# HighSideDriver.net
KiCad netlist of a schematic drawn in Altium Designer
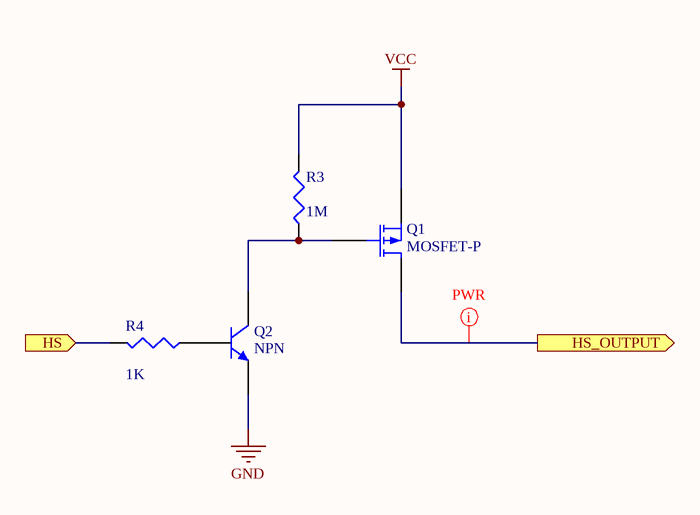
[diagram p0: HighSideDriver.SchDoc]

(export (version "E")
  (design (tool "Eeschema 10.0.6"))
  (components
    (comp (ref "Q1")
      (value "MOSFET-P")
      (footprint "SOT23_M")
      (description "P-Channel MOSFET")
      (fields (field (name "PUBLISHER") "Altium Limited"))
      (libsource (lib "Miscellaneous Devices") (part "MOSFET-P"))
    )
    (comp (ref "Q2")
      (value "NPN")
      (footprint "SOT-23B_M")
      (description "NPN Bipolar Transistor")
      (fields (field (name "PUBLISHER") "Altium Limited"))
      (libsource (lib "Miscellaneous Devices") (part "NPN"))
    )
    (comp (ref "R3")
      (value "1M")
      (footprint "1608[0603]")
      (description "Resistor")
      (fields (field (name "Comment") "Res3") (field (name "PUBLISHER") "Altium Limited"))
      (libsource (lib "Miscellaneous Devices") (part "Res3"))
    )
    (comp (ref "R4")
      (value "1K")
      (footprint "1608[0603]")
      (description "Resistor")
      (fields (field (name "Comment") "Res3") (field (name "PUBLISHER") "Altium Limited"))
      (libsource (lib "Miscellaneous Devices") (part "Res3"))
    )
  )
  (nets
    (net (code "1") (name "/HS") (class "Default")
      (node (ref "R4") (pin "2") (pinfunction "2_2") (pintype "passive"))
    )
    (net (code "2") (name "/HS_OUTPUT") (class "Default")
      (node (ref "Q1") (pin "1") (pinfunction "D_1") (pintype "passive"))
    )
    (net (code "3") (name "GND") (class "Default")
      (node (ref "Q2") (pin "3") (pinfunction "E_3") (pintype "passive"))
    )
    (net (code "4") (name "Net-(Q1-G)") (class "Default")
      (node (ref "Q1") (pin "2") (pinfunction "G_2") (pintype "passive"))
      (node (ref "Q2") (pin "1") (pinfunction "C_1") (pintype "passive"))
      (node (ref "R3") (pin "1") (pinfunction "1_1") (pintype "passive"))
    )
    (net (code "5") (name "Net-(Q2-B)") (class "Default")
      (node (ref "Q2") (pin "2") (pinfunction "B_2") (pintype "passive"))
      (node (ref "R4") (pin "1") (pinfunction "1_1") (pintype "passive"))
    )
    (net (code "6") (name "VCC") (class "Default")
      (node (ref "Q1") (pin "3") (pinfunction "S_3") (pintype "passive"))
      (node (ref "R3") (pin "2") (pinfunction "2_2") (pintype "passive"))
    )
  )
)
